# BMS_Cell.net
KiCad netlist of a schematic drawn in Altium Designer
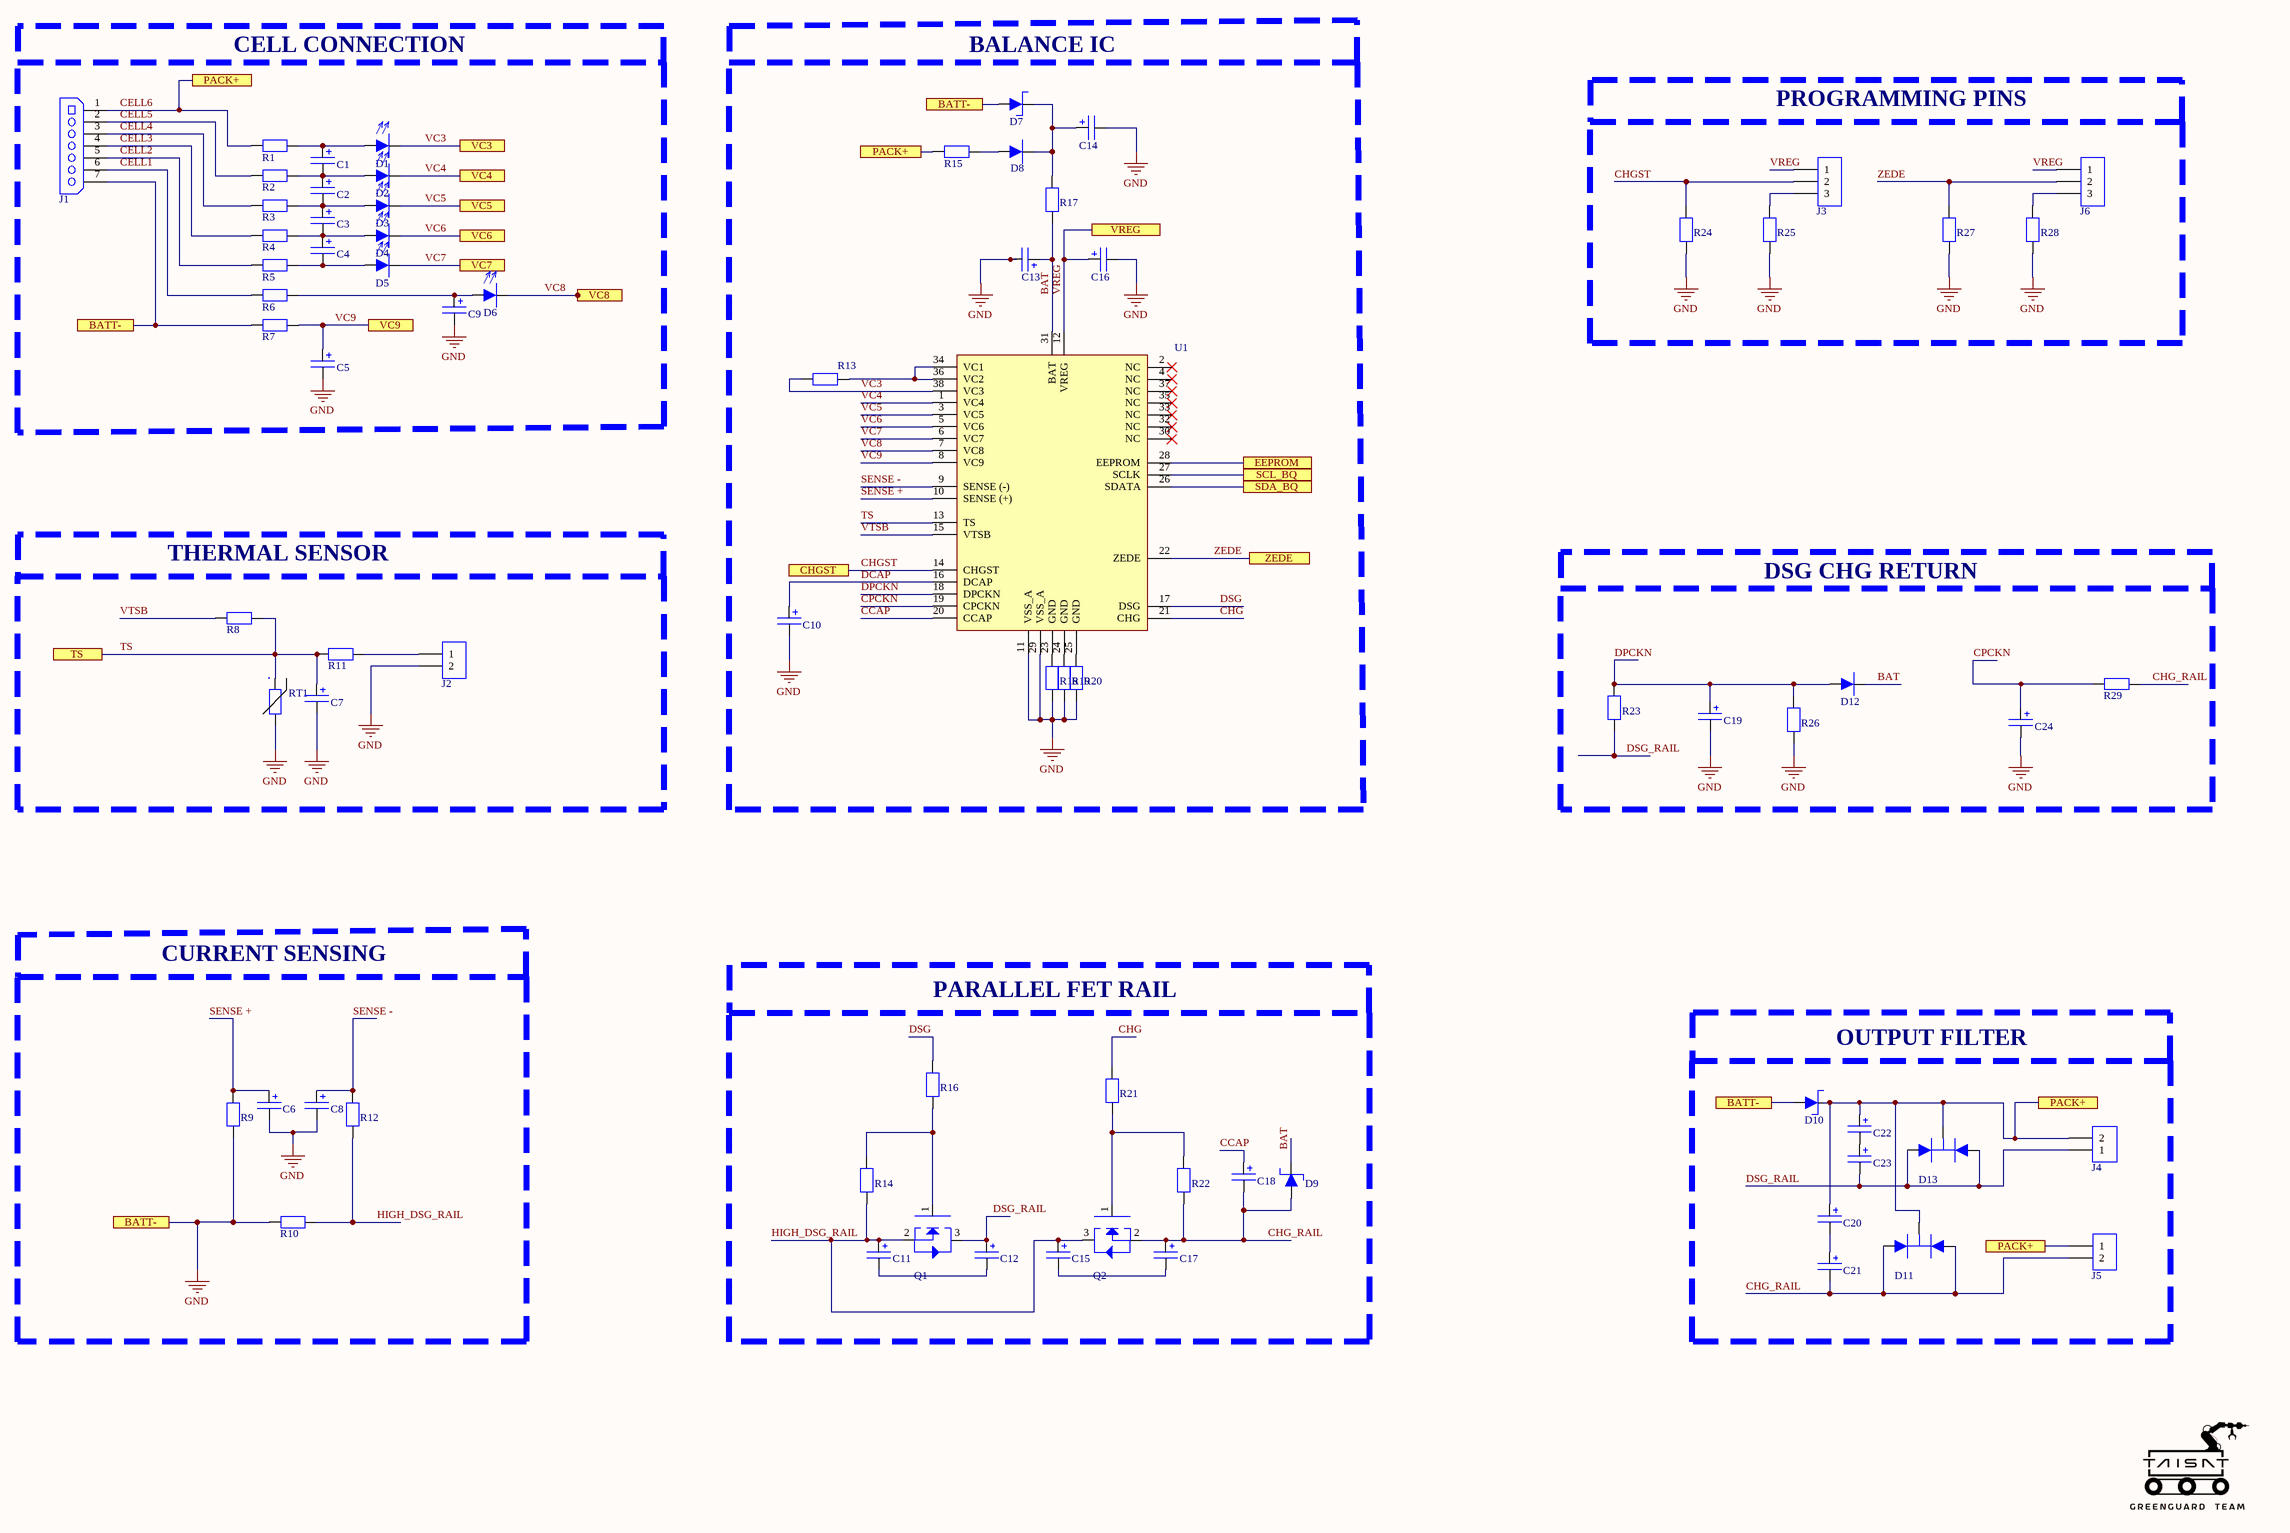
[diagram p0: BMS_Cell.SchDoc]

(export (version "E")
  (design (tool "Eeschema 10.0.6"))
  (components
    (comp (ref "C1")
      (value "1uF")
      (footprint "CAP 0805")
      (description "Multilayer Ceramic Capacitor")
      (fields
        (field (name "MANUFACTURER") "KEMET")
        (field (name "MANUFACTURER PART NUMBER") "C0805C224K5RACTU")
        (field (name "CREATED BY") "Kaptanyum")
      )
      (libsource (lib "Kaptanyums Lib") (part "CAP 0805"))
    )
    (comp (ref "C2")
      (value "1uF")
      (footprint "CAP 0805")
      (description "Multilayer Ceramic Capacitor")
      (fields
        (field (name "MANUFACTURER") "KEMET")
        (field (name "MANUFACTURER PART NUMBER") "C0805C224K5RACTU")
        (field (name "CREATED BY") "Kaptanyum")
      )
      (libsource (lib "Kaptanyums Lib") (part "CAP 0805"))
    )
    (comp (ref "C3")
      (value "1uF")
      (footprint "CAP 0805")
      (description "Multilayer Ceramic Capacitor")
      (fields
        (field (name "MANUFACTURER") "KEMET")
        (field (name "MANUFACTURER PART NUMBER") "C0805C224K5RACTU")
        (field (name "CREATED BY") "Kaptanyum")
      )
      (libsource (lib "Kaptanyums Lib") (part "CAP 0805"))
    )
    (comp (ref "C4")
      (value "1uF")
      (footprint "CAP 0805")
      (description "Multilayer Ceramic Capacitor")
      (fields
        (field (name "MANUFACTURER") "KEMET")
        (field (name "MANUFACTURER PART NUMBER") "C0805C224K5RACTU")
        (field (name "CREATED BY") "Kaptanyum")
      )
      (libsource (lib "Kaptanyums Lib") (part "CAP 0805"))
    )
    (comp (ref "C5")
      (value "1uF")
      (footprint "CAP 0805")
      (description "Multilayer Ceramic Capacitor")
      (fields
        (field (name "MANUFACTURER") "KEMET")
        (field (name "MANUFACTURER PART NUMBER") "C0805C224K5RACTU")
        (field (name "CREATED BY") "Kaptanyum")
      )
      (libsource (lib "Kaptanyums Lib") (part "CAP 0805"))
    )
    (comp (ref "C6")
      (value "0.1uF")
      (footprint "CAP 0603")
      (description "Multilayer Ceramic Capacitor")
      (fields
        (field (name "MANUFACTURER") "KEMET")
        (field (name "MANUFACTURER PART NUMBER") "C0603C103K5RACTU")
        (field (name "CREATED BY") "Kaptanyum")
      )
      (libsource (lib "Kaptanyums Lib") (part "CAP 0603"))
    )
    (comp (ref "C7")
      (value "10nF")
      (footprint "CAP 0603")
      (description "Multilayer Ceramic Capacitor")
      (fields
        (field (name "MANUFACTURER") "KEMET")
        (field (name "MANUFACTURER PART NUMBER") "C0603C103K5RACTU")
        (field (name "CREATED BY") "Kaptanyum")
      )
      (libsource (lib "Kaptanyums Lib") (part "CAP 0603"))
    )
    (comp (ref "C8")
      (value "0.1uF")
      (footprint "CAP 0603")
      (description "Multilayer Ceramic Capacitor")
      (fields
        (field (name "MANUFACTURER") "KEMET")
        (field (name "MANUFACTURER PART NUMBER") "C0603C103K5RACTU")
        (field (name "CREATED BY") "Kaptanyum")
      )
      (libsource (lib "Kaptanyums Lib") (part "CAP 0603"))
    )
    (comp (ref "C9")
      (value "1uF")
      (footprint "CAP 0805")
      (description "Multilayer Ceramic Capacitor")
      (fields
        (field (name "MANUFACTURER") "KEMET")
        (field (name "MANUFACTURER PART NUMBER") "C0805C224K5RACTU")
        (field (name "CREATED BY") "Kaptanyum")
      )
      (libsource (lib "Kaptanyums Lib") (part "CAP 0805"))
    )
    (comp (ref "C10")
      (value "1uF")
      (footprint "CAP 0603")
      (description "Multilayer Ceramic Capacitor")
      (fields
        (field (name "MANUFACTURER") "KEMET")
        (field (name "MANUFACTURER PART NUMBER") "C0603C103K5RACTU")
        (field (name "CREATED BY") "Kaptanyum")
      )
      (libsource (lib "Kaptanyums Lib") (part "CAP 0603"))
    )
    (comp (ref "C11")
      (value "0.1uF")
      (footprint "CAP 0603")
      (description "Multilayer Ceramic Capacitor")
      (fields
        (field (name "MANUFACTURER") "KEMET")
        (field (name "MANUFACTURER PART NUMBER") "C0603C103K5RACTU")
        (field (name "CREATED BY") "Kaptanyum")
      )
      (libsource (lib "Kaptanyums Lib") (part "CAP 0603"))
    )
    (comp (ref "C12")
      (value "0.1uF")
      (footprint "CAP 0603")
      (description "Multilayer Ceramic Capacitor")
      (fields
        (field (name "MANUFACTURER") "KEMET")
        (field (name "MANUFACTURER PART NUMBER") "C0603C103K5RACTU")
        (field (name "CREATED BY") "Kaptanyum")
      )
      (libsource (lib "Kaptanyums Lib") (part "CAP 0603"))
    )
    (comp (ref "C13")
      (value "0.1uF")
      (footprint "CAP 0603")
      (description "Multilayer Ceramic Capacitor")
      (fields
        (field (name "MANUFACTURER") "KEMET")
        (field (name "MANUFACTURER PART NUMBER") "C0603C103K5RACTU")
        (field (name "CREATED BY") "Kaptanyum")
      )
      (libsource (lib "Kaptanyums Lib") (part "CAP 0603"))
    )
    (comp (ref "C14")
      (value "10uF")
      (footprint "CAP 0603")
      (description "Multilayer Ceramic Capacitor")
      (fields
        (field (name "MANUFACTURER") "KEMET")
        (field (name "MANUFACTURER PART NUMBER") "C0603C103K5RACTU")
        (field (name "CREATED BY") "Kaptanyum")
      )
      (libsource (lib "Kaptanyums Lib") (part "CAP 0603"))
    )
    (comp (ref "C15")
      (value "0.1uF")
      (footprint "CAP 0603")
      (description "Multilayer Ceramic Capacitor")
      (fields
        (field (name "MANUFACTURER") "KEMET")
        (field (name "MANUFACTURER PART NUMBER") "C0603C103K5RACTU")
        (field (name "CREATED BY") "Kaptanyum")
      )
      (libsource (lib "Kaptanyums Lib") (part "CAP 0603"))
    )
    (comp (ref "C16")
      (value "4.7uF")
      (footprint "CAP 0603")
      (description "Multilayer Ceramic Capacitor")
      (fields
        (field (name "MANUFACTURER") "KEMET")
        (field (name "MANUFACTURER PART NUMBER") "C0603C103K5RACTU")
        (field (name "CREATED BY") "Kaptanyum")
      )
      (libsource (lib "Kaptanyums Lib") (part "CAP 0603"))
    )
    (comp (ref "C17")
      (value "0.1uF")
      (footprint "CAP 0603")
      (description "Multilayer Ceramic Capacitor")
      (fields
        (field (name "MANUFACTURER") "KEMET")
        (field (name "MANUFACTURER PART NUMBER") "C0603C103K5RACTU")
        (field (name "CREATED BY") "Kaptanyum")
      )
      (libsource (lib "Kaptanyums Lib") (part "CAP 0603"))
    )
    (comp (ref "C18")
      (value "1uF")
      (footprint "CAP 0603")
      (description "Multilayer Ceramic Capacitor")
      (fields
        (field (name "MANUFACTURER") "KEMET")
        (field (name "MANUFACTURER PART NUMBER") "C0603C103K5RACTU")
        (field (name "CREATED BY") "Kaptanyum")
      )
      (libsource (lib "Kaptanyums Lib") (part "CAP 0603"))
    )
    (comp (ref "C19")
      (value "0.1uF")
      (footprint "CAP 0603")
      (description "Multilayer Ceramic Capacitor")
      (fields
        (field (name "MANUFACTURER") "KEMET")
        (field (name "MANUFACTURER PART NUMBER") "C0603C103K5RACTU")
        (field (name "CREATED BY") "Kaptanyum")
      )
      (libsource (lib "Kaptanyums Lib") (part "CAP 0603"))
    )
    (comp (ref "C20")
      (value "0.1uF")
      (footprint "CAP 0603")
      (description "Multilayer Ceramic Capacitor")
      (fields
        (field (name "MANUFACTURER") "KEMET")
        (field (name "MANUFACTURER PART NUMBER") "C0603C103K5RACTU")
        (field (name "CREATED BY") "Kaptanyum")
      )
      (libsource (lib "Kaptanyums Lib") (part "CAP 0603"))
    )
    (comp (ref "C21")
      (value "0.1uF")
      (footprint "CAP 0603")
      (description "Multilayer Ceramic Capacitor")
      (fields
        (field (name "MANUFACTURER") "KEMET")
        (field (name "MANUFACTURER PART NUMBER") "C0603C103K5RACTU")
        (field (name "CREATED BY") "Kaptanyum")
      )
      (libsource (lib "Kaptanyums Lib") (part "CAP 0603"))
    )
    (comp (ref "C22")
      (value "0.1uF")
      (footprint "CAP 0603")
      (description "Multilayer Ceramic Capacitor")
      (fields
        (field (name "MANUFACTURER") "KEMET")
        (field (name "MANUFACTURER PART NUMBER") "C0603C103K5RACTU")
        (field (name "CREATED BY") "Kaptanyum")
      )
      (libsource (lib "Kaptanyums Lib") (part "CAP 0603"))
    )
    (comp (ref "C23")
      (value "0.1uF")
      (footprint "CAP 0603")
      (description "Multilayer Ceramic Capacitor")
      (fields
        (field (name "MANUFACTURER") "KEMET")
        (field (name "MANUFACTURER PART NUMBER") "C0603C103K5RACTU")
        (field (name "CREATED BY") "Kaptanyum")
      )
      (libsource (lib "Kaptanyums Lib") (part "CAP 0603"))
    )
    (comp (ref "C24")
      (value "0.1uF")
      (footprint "CAP 0603")
      (description "Multilayer Ceramic Capacitor")
      (fields
        (field (name "MANUFACTURER") "KEMET")
        (field (name "MANUFACTURER PART NUMBER") "C0603C103K5RACTU")
        (field (name "CREATED BY") "Kaptanyum")
      )
      (libsource (lib "Kaptanyums Lib") (part "CAP 0603"))
    )
    (comp (ref "D1")
      (value "LTW-C191TLA")
      (footprint "LED 0603")
      (description "Chip LED")
      (fields
        (field (name "MANUFACTURER") "Vishay Lite-On")
        (field (name "MANUFACTURER PART NUMBER") "LTST-C190GKT")
        (field (name "CREATED BY") "Kaptanyum")
      )
      (libsource (lib "Schlib") (part "LED 0603"))
    )
    (comp (ref "D2")
      (value "LTW-C191TLA")
      (footprint "LED 0603")
      (description "Chip LED")
      (fields
        (field (name "MANUFACTURER") "Vishay Lite-On")
        (field (name "MANUFACTURER PART NUMBER") "LTST-C190GKT")
        (field (name "CREATED BY") "Kaptanyum")
      )
      (libsource (lib "Schlib") (part "LED 0603"))
    )
    (comp (ref "D3")
      (value "LTW-C191TLA")
      (footprint "LED 0603")
      (description "Chip LED")
      (fields
        (field (name "MANUFACTURER") "Vishay Lite-On")
        (field (name "MANUFACTURER PART NUMBER") "LTST-C190GKT")
        (field (name "CREATED BY") "Kaptanyum")
      )
      (libsource (lib "Schlib") (part "LED 0603"))
    )
    (comp (ref "D4")
      (value "LTW-C191TLA")
      (footprint "LED 0603")
      (description "Chip LED")
      (fields
        (field (name "MANUFACTURER") "Vishay Lite-On")
        (field (name "MANUFACTURER PART NUMBER") "LTST-C190GKT")
        (field (name "CREATED BY") "Kaptanyum")
      )
      (libsource (lib "Schlib") (part "LED 0603"))
    )
    (comp (ref "D5")
      (value "LTW-C191TLA")
      (footprint "LED 0603")
      (description "Chip LED")
      (fields
        (field (name "MANUFACTURER") "Vishay Lite-On")
        (field (name "MANUFACTURER PART NUMBER") "LTST-C190GKT")
        (field (name "CREATED BY") "Kaptanyum")
      )
      (libsource (lib "Schlib") (part "LED 0603"))
    )
    (comp (ref "D6")
      (value "LTW-C191TLA")
      (footprint "LED 0603")
      (description "Chip LED")
      (fields
        (field (name "MANUFACTURER") "Vishay Lite-On")
        (field (name "MANUFACTURER PART NUMBER") "LTST-C190GKT")
        (field (name "CREATED BY") "Kaptanyum")
      )
      (libsource (lib "Schlib") (part "LED 0603"))
    )
    (comp (ref "D7")
      (value "SMAJ36A-HT")
      (footprint "DO214AC")
      (description "Diode TVS 36V")
      (fields
        (field (name "MANUFACTURER") "Vishay Semiconductors")
        (field (name "MANUFACTURER PART NUMBER") "SMAJ36AHE3/61")
      )
      (libsource (lib "Schlib") (part "SMAJ36A-HT"))
    )
    (comp (ref "D8")
      (value "1N4148WS-HT")
      (footprint "SOD323")
      (description "Diode Switch 75V")
      (libsource (lib "Kaptanyums Lib") (part "1N4148WS-HT"))
    )
    (comp (ref "D9")
      (value "SMAJ36A-HT")
      (footprint "DO214AC")
      (description "Diode TVS 36V")
      (fields
        (field (name "MANUFACTURER") "Vishay Semiconductors")
        (field (name "MANUFACTURER PART NUMBER") "SMAJ36AHE3/61")
      )
      (libsource (lib "Schlib") (part "SMAJ36A-HT"))
    )
    (comp (ref "D10")
      (value "SMAJ36A-HT")
      (footprint "DO214AC")
      (description "Diode TVS 36V")
      (fields
        (field (name "MANUFACTURER") "Vishay Semiconductors")
        (field (name "MANUFACTURER PART NUMBER") "SMAJ36AHE3/61")
      )
      (libsource (lib "Schlib") (part "SMAJ36A-HT"))
    )
    (comp (ref "D11")
      (value "BYQ28ED")
      (footprint "DPAK")
      (description "Diode Array Rectifier")
      (fields
        (field (name "MANUFACTURER") "NXP Semiconductors")
        (field (name "MANUFACTURER PART NUMBER") "BYQ28ED-200/T3")
        (field (name "CREATED BY") "Kaptanyum")
      )
      (libsource (lib "Kaptanyums Lib") (part "BYQ28ED"))
    )
    (comp (ref "D12")
      (value "1N4148WS-HT")
      (footprint "SOD323")
      (description "Diode Switch 75V")
      (libsource (lib "Kaptanyums Lib") (part "1N4148WS-HT"))
    )
    (comp (ref "D13")
      (value "BYQ28ED")
      (footprint "DPAK")
      (description "Diode Array Rectifier")
      (fields
        (field (name "MANUFACTURER") "NXP Semiconductors")
        (field (name "MANUFACTURER PART NUMBER") "BYQ28ED-200/T3")
        (field (name "CREATED BY") "Kaptanyum")
      )
      (libsource (lib "Kaptanyums Lib") (part "BYQ28ED"))
    )
    (comp (ref "J1")
      (value "JST-XH-7")
      (footprint "JST-XH-7")
      (description "JST Socket for PCB")
      (fields
        (field (name "MANUFACTURER") "JST")
        (field (name "MANUFACTURER PART NUMBER") "B4B-XH-A(LF)(SN)")
        (field (name "CREATED BY") "Kaptanyum")
      )
      (libsource (lib "Kaptanyums Lib") (part "JST-XH-7"))
    )
    (comp (ref "J2")
      (value "146285-2")
      (footprint "HEADER 1x2")
      (description "Header for PCB")
      (fields
        (field (name "MANUFACTURER") "JST")
        (field (name "MANUFACTURER PART NUMBER") "B4B-XH-A(LF)(SN)")
        (field (name "CREATED BY") "Kaptanyum")
      )
      (libsource (lib "Kaptanyums Lib") (part "HEADER 1x2"))
    )
    (comp (ref "J3")
      (value "146285-3")
      (footprint "HEADER 1x3")
      (description "Header for PCB")
      (fields
        (field (name "MANUFACTURER") "JST")
        (field (name "MANUFACTURER PART NUMBER") "B4B-XH-A(LF)(SN)")
        (field (name "CREATED BY") "Kaptanyum")
      )
      (libsource (lib "Kaptanyums Lib") (part "HEADER 1x3"))
    )
    (comp (ref "J4")
      (value "282845-2")
      (footprint "Terminal 1x2")
      (description "7.62mm 2 POS")
      (fields (field (name "CREATED BY") "Kaptanyum"))
      (libsource (lib "Kaptanyums Lib") (part "SCREW TERMINAL"))
    )
    (comp (ref "J5")
      (value "282845-2")
      (footprint "Terminal 1x2")
      (description "7.62mm 2 POS")
      (fields (field (name "CREATED BY") "Kaptanyum"))
      (libsource (lib "Kaptanyums Lib") (part "SCREW TERMINAL"))
    )
    (comp (ref "J6")
      (value "146285-3")
      (footprint "HEADER 1x3")
      (description "Header for PCB")
      (fields
        (field (name "MANUFACTURER") "JST")
        (field (name "MANUFACTURER PART NUMBER") "B4B-XH-A(LF)(SN)")
        (field (name "CREATED BY") "Kaptanyum")
      )
      (libsource (lib "Kaptanyums Lib") (part "HEADER 1x3"))
    )
    (comp (ref "Q1")
      (value "IRF540SPBF")
      (footprint "D2PAK-3")
      (description "MOSFET N-ch, 100V 28A")
      (libsource (lib "Kaptanyums Lib") (part "IRF540SPBF"))
    )
    (comp (ref "Q2")
      (value "IRF540SPBF")
      (footprint "D2PAK-3")
      (description "MOSFET N-ch, 100V 28A")
      (libsource (lib "Kaptanyums Lib") (part "IRF540SPBF"))
    )
    (comp (ref "R1")
      (value "500R")
      (footprint "RESISTOR 1206")
      (description "SMD Chip Resistor")
      (fields
        (field (name "MANUFACTURER") "Yageo")
        (field (name "MANUFACTURER PART NUMBER") "RC1206FR-074K7L")
        (field (name "CREATED BY") "Kaptanyum")
      )
      (libsource (lib "Kaptanyums Lib") (part "RES 1206"))
    )
    (comp (ref "R2")
      (value "500R")
      (footprint "RESISTOR 1206")
      (description "SMD Chip Resistor")
      (fields
        (field (name "MANUFACTURER") "Yageo")
        (field (name "MANUFACTURER PART NUMBER") "RC1206FR-074K7L")
        (field (name "CREATED BY") "Kaptanyum")
      )
      (libsource (lib "Kaptanyums Lib") (part "RES 1206"))
    )
    (comp (ref "R3")
      (value "500R")
      (footprint "RESISTOR 1206")
      (description "SMD Chip Resistor")
      (fields
        (field (name "MANUFACTURER") "Yageo")
        (field (name "MANUFACTURER PART NUMBER") "RC1206FR-074K7L")
        (field (name "CREATED BY") "Kaptanyum")
      )
      (libsource (lib "Kaptanyums Lib") (part "RES 1206"))
    )
    (comp (ref "R4")
      (value "500R")
      (footprint "RESISTOR 1206")
      (description "SMD Chip Resistor")
      (fields
        (field (name "MANUFACTURER") "Yageo")
        (field (name "MANUFACTURER PART NUMBER") "RC1206FR-074K7L")
        (field (name "CREATED BY") "Kaptanyum")
      )
      (libsource (lib "Kaptanyums Lib") (part "RES 1206"))
    )
    (comp (ref "R5")
      (value "500R")
      (footprint "RESISTOR 1206")
      (description "SMD Chip Resistor")
      (fields
        (field (name "MANUFACTURER") "Yageo")
        (field (name "MANUFACTURER PART NUMBER") "RC1206FR-074K7L")
        (field (name "CREATED BY") "Kaptanyum")
      )
      (libsource (lib "Kaptanyums Lib") (part "RES 1206"))
    )
    (comp (ref "R6")
      (value "500R")
      (footprint "RESISTOR 1206")
      (description "SMD Chip Resistor")
      (fields
        (field (name "MANUFACTURER") "Yageo")
        (field (name "MANUFACTURER PART NUMBER") "RC1206FR-074K7L")
        (field (name "CREATED BY") "Kaptanyum")
      )
      (libsource (lib "Kaptanyums Lib") (part "RES 1206"))
    )
    (comp (ref "R7")
      (value "500R")
      (footprint "RESISTOR 1206")
      (description "SMD Chip Resistor")
      (fields
        (field (name "MANUFACTURER") "Yageo")
        (field (name "MANUFACTURER PART NUMBER") "RC1206FR-074K7L")
        (field (name "CREATED BY") "Kaptanyum")
      )
      (libsource (lib "Kaptanyums Lib") (part "RES 1206"))
    )
    (comp (ref "R8")
      (value "10K")
      (footprint "RESISTOR 0603")
      (description "SMD Chip Resistor")
      (fields
        (field (name "MANUFACTURER") "Yageo")
        (field (name "MANUFACTURER PART NUMBER") "AC0603FR-071KL")
        (field (name "CREATED BY") "Kaptanyum")
      )
      (libsource (lib "Kaptanyums Lib") (part "RES 0603"))
    )
    (comp (ref "R9")
      (value "1K")
      (footprint "RESISTOR 0603")
      (description "SMD Chip Resistor")
      (fields
        (field (name "MANUFACTURER") "Yageo")
        (field (name "MANUFACTURER PART NUMBER") "AC0603FR-071KL")
        (field (name "CREATED BY") "Kaptanyum")
      )
      (libsource (lib "Kaptanyums Lib") (part "RES 0603"))
    )
    (comp (ref "R10")
      (value "0.002R Shunt")
      (footprint "RESISTOR 2512")
      (description "SMD Chip Resistor")
      (fields
        (field (name "MANUFACTURER") "Yageo")
        (field (name "MANUFACTURER PART NUMBER") "RC1206FR-074K7L")
        (field (name "CREATED BY") "Kaptanyum")
      )
      (libsource (lib "Kaptanyums Lib") (part "RES 2512"))
    )
    (comp (ref "R11")
      (value "50R")
      (footprint "RESISTOR 0603")
      (description "SMD Chip Resistor")
      (fields
        (field (name "MANUFACTURER") "Yageo")
        (field (name "MANUFACTURER PART NUMBER") "AC0603FR-071KL")
        (field (name "CREATED BY") "Kaptanyum")
      )
      (libsource (lib "Kaptanyums Lib") (part "RES 0603"))
    )
    (comp (ref "R12")
      (value "1K")
      (footprint "RESISTOR 0603")
      (description "SMD Chip Resistor")
      (fields
        (field (name "MANUFACTURER") "Yageo")
        (field (name "MANUFACTURER PART NUMBER") "AC0603FR-071KL")
        (field (name "CREATED BY") "Kaptanyum")
      )
      (libsource (lib "Kaptanyums Lib") (part "RES 0603"))
    )
    (comp (ref "R13")
      (value "100R")
      (footprint "RESISTOR 0603")
      (description "SMD Chip Resistor")
      (fields
        (field (name "MANUFACTURER") "Yageo")
        (field (name "MANUFACTURER PART NUMBER") "AC0603FR-071KL")
        (field (name "CREATED BY") "Kaptanyum")
      )
      (libsource (lib "Kaptanyums Lib") (part "RES 0603"))
    )
    (comp (ref "R14")
      (value "5.1M")
      (footprint "RESISTOR 0603")
      (description "SMD Chip Resistor")
      (fields
        (field (name "MANUFACTURER") "Yageo")
        (field (name "MANUFACTURER PART NUMBER") "AC0603FR-071KL")
        (field (name "CREATED BY") "Kaptanyum")
      )
      (libsource (lib "Kaptanyums Lib") (part "RES 0603"))
    )
    (comp (ref "R15")
      (value "200R")
      (footprint "RESISTOR 0603")
      (description "SMD Chip Resistor")
      (fields
        (field (name "MANUFACTURER") "Yageo")
        (field (name "MANUFACTURER PART NUMBER") "AC0603FR-071KL")
        (field (name "CREATED BY") "Kaptanyum")
      )
      (libsource (lib "Kaptanyums Lib") (part "RES 0603"))
    )
    (comp (ref "R16")
      (value "1K")
      (footprint "RESISTOR 0603")
      (description "SMD Chip Resistor")
      (fields
        (field (name "MANUFACTURER") "Yageo")
        (field (name "MANUFACTURER PART NUMBER") "AC0603FR-071KL")
        (field (name "CREATED BY") "Kaptanyum")
      )
      (libsource (lib "Kaptanyums Lib") (part "RES 0603"))
    )
    (comp (ref "R17")
      (value "100R")
      (footprint "RESISTOR 0603")
      (description "SMD Chip Resistor")
      (fields
        (field (name "MANUFACTURER") "Yageo")
        (field (name "MANUFACTURER PART NUMBER") "AC0603FR-071KL")
        (field (name "CREATED BY") "Kaptanyum")
      )
      (libsource (lib "Kaptanyums Lib") (part "RES 0603"))
    )
    (comp (ref "R18")
      (value "1K")
      (footprint "RESISTOR 0603")
      (description "SMD Chip Resistor")
      (fields
        (field (name "MANUFACTURER") "Yageo")
        (field (name "MANUFACTURER PART NUMBER") "AC0603FR-071KL")
        (field (name "CREATED BY") "Kaptanyum")
      )
      (libsource (lib "Kaptanyums Lib") (part "RES 0603"))
    )
    (comp (ref "R19")
      (value "1K")
      (footprint "RESISTOR 0603")
      (description "SMD Chip Resistor")
      (fields
        (field (name "MANUFACTURER") "Yageo")
        (field (name "MANUFACTURER PART NUMBER") "AC0603FR-071KL")
        (field (name "CREATED BY") "Kaptanyum")
      )
      (libsource (lib "Kaptanyums Lib") (part "RES 0603"))
    )
    (comp (ref "R20")
      (value "1K")
      (footprint "RESISTOR 0603")
      (description "SMD Chip Resistor")
      (fields
        (field (name "MANUFACTURER") "Yageo")
        (field (name "MANUFACTURER PART NUMBER") "AC0603FR-071KL")
        (field (name "CREATED BY") "Kaptanyum")
      )
      (libsource (lib "Kaptanyums Lib") (part "RES 0603"))
    )
    (comp (ref "R21")
      (value "1K")
      (footprint "RESISTOR 0603")
      (description "SMD Chip Resistor")
      (fields
        (field (name "MANUFACTURER") "Yageo")
        (field (name "MANUFACTURER PART NUMBER") "AC0603FR-071KL")
        (field (name "CREATED BY") "Kaptanyum")
      )
      (libsource (lib "Kaptanyums Lib") (part "RES 0603"))
    )
    (comp (ref "R22")
      (value "5.1M")
      (footprint "RESISTOR 0603")
      (description "SMD Chip Resistor")
      (fields
        (field (name "MANUFACTURER") "Yageo")
        (field (name "MANUFACTURER PART NUMBER") "AC0603FR-071KL")
        (field (name "CREATED BY") "Kaptanyum")
      )
      (libsource (lib "Kaptanyums Lib") (part "RES 0603"))
    )
    (comp (ref "R23")
      (value "100R")
      (footprint "RESISTOR 0603")
      (description "SMD Chip Resistor")
      (fields
        (field (name "MANUFACTURER") "Yageo")
        (field (name "MANUFACTURER PART NUMBER") "AC0603FR-071KL")
        (field (name "CREATED BY") "Kaptanyum")
      )
      (libsource (lib "Kaptanyums Lib") (part "RES 0603"))
    )
    (comp (ref "R24")
      (value "1K")
      (footprint "RESISTOR 0603")
      (description "SMD Chip Resistor")
      (fields
        (field (name "MANUFACTURER") "Yageo")
        (field (name "MANUFACTURER PART NUMBER") "AC0603FR-071KL")
        (field (name "CREATED BY") "Kaptanyum")
      )
      (libsource (lib "Kaptanyums Lib") (part "RES 0603"))
    )
    (comp (ref "R25")
      (value "1K")
      (footprint "RESISTOR 0603")
      (description "SMD Chip Resistor")
      (fields
        (field (name "MANUFACTURER") "Yageo")
        (field (name "MANUFACTURER PART NUMBER") "AC0603FR-071KL")
        (field (name "CREATED BY") "Kaptanyum")
      )
      (libsource (lib "Kaptanyums Lib") (part "RES 0603"))
    )
    (comp (ref "R26")
      (value "47K")
      (footprint "RESISTOR 0603")
      (description "SMD Chip Resistor")
      (fields
        (field (name "MANUFACTURER") "Yageo")
        (field (name "MANUFACTURER PART NUMBER") "AC0603FR-071KL")
        (field (name "CREATED BY") "Kaptanyum")
      )
      (libsource (lib "Kaptanyums Lib") (part "RES 0603"))
    )
    (comp (ref "R27")
      (value "1K")
      (footprint "RESISTOR 0603")
      (description "SMD Chip Resistor")
      (fields
        (field (name "MANUFACTURER") "Yageo")
        (field (name "MANUFACTURER PART NUMBER") "AC0603FR-071KL")
        (field (name "CREATED BY") "Kaptanyum")
      )
      (libsource (lib "Kaptanyums Lib") (part "RES 0603"))
    )
    (comp (ref "R28")
      (value "1K")
      (footprint "RESISTOR 0603")
      (description "SMD Chip Resistor")
      (fields
        (field (name "MANUFACTURER") "Yageo")
        (field (name "MANUFACTURER PART NUMBER") "AC0603FR-071KL")
        (field (name "CREATED BY") "Kaptanyum")
      )
      (libsource (lib "Kaptanyums Lib") (part "RES 0603"))
    )
    (comp (ref "R29")
      (value "100R")
      (footprint "RESISTOR 0603")
      (description "SMD Chip Resistor")
      (fields
        (field (name "MANUFACTURER") "Yageo")
        (field (name "MANUFACTURER PART NUMBER") "AC0603FR-071KL")
        (field (name "CREATED BY") "Kaptanyum")
      )
      (libsource (lib "Kaptanyums Lib") (part "RES 0603"))
    )
    (comp (ref "RT1")
      (value "10K")
      (footprint "NTC 0603")
      (description "Thermistor NTC")
      (fields
        (field (name "MANUFACTURER") "Panasonic")
        (field (name "MANUFACTURER PART NUMBER") "ERT-J1VG103FA")
        (field (name "CREATED BY") "Kaptanyum")
      )
      (libsource (lib "Kaptanyums Lib") (part "NTC 0603"))
    )
    (comp (ref "U1")
      (value "BQ77908")
      (footprint "TSSOP-38")
      (description "Cell Balance, Cell Monitoring")
      (fields
        (field (name "MANUFACTURER") "Texas Instruments")
        (field (name "MANUFACTURER PART NUMBER") "BQ77908ADBTR")
        (field (name "CREATED BY") "Kaptanyum")
      )
      (libsource (lib "Kaptanyums Lib") (part "BQ77908"))
    )
  )
  (nets
    (net (code "1") (name "/BAT") (class "Default")
      (node (ref "C13") (pin "1") (pinfunction "1_1") (pintype "passive"))
      (node (ref "D12") (pin "1") (pinfunction "1_1") (pintype "passive"))
      (node (ref "D9") (pin "1") (pinfunction "1_1") (pintype "passive"))
      (node (ref "R17") (pin "1") (pinfunction "1_1") (pintype "passive"))
      (node (ref "U1") (pin "31") (pinfunction "BAT_31") (pintype "passive"))
    )
    (net (code "2") (name "/CCAP") (class "Default")
      (node (ref "C18") (pin "1") (pinfunction "1_1") (pintype "passive"))
      (node (ref "U1") (pin "20") (pinfunction "CCAP_20") (pintype "passive"))
    )
    (net (code "3") (name "/CELL1") (class "Default")
      (node (ref "J1") (pin "6") (pinfunction "6_6") (pintype "passive"))
      (node (ref "R6") (pin "1") (pinfunction "1_1") (pintype "passive"))
    )
    (net (code "4") (name "/CELL2") (class "Default")
      (node (ref "J1") (pin "5") (pinfunction "5_5") (pintype "passive"))
      (node (ref "R5") (pin "1") (pinfunction "1_1") (pintype "passive"))
    )
    (net (code "5") (name "/CELL3") (class "Default")
      (node (ref "J1") (pin "4") (pinfunction "4_4") (pintype "passive"))
      (node (ref "R4") (pin "1") (pinfunction "1_1") (pintype "passive"))
    )
    (net (code "6") (name "/CELL4") (class "Default")
      (node (ref "J1") (pin "3") (pinfunction "3_3") (pintype "passive"))
      (node (ref "R3") (pin "1") (pinfunction "1_1") (pintype "passive"))
    )
    (net (code "7") (name "/CELL5") (class "Default")
      (node (ref "J1") (pin "2") (pinfunction "2_2") (pintype "passive"))
      (node (ref "R2") (pin "1") (pinfunction "1_1") (pintype "passive"))
    )
    (net (code "8") (name "/CELL6") (class "Default")
      (node (ref "C20") (pin "1") (pinfunction "1_1") (pintype "passive"))
      (node (ref "C22") (pin "1") (pinfunction "1_1") (pintype "passive"))
      (node (ref "D10") (pin "1") (pinfunction "1_1") (pintype "passive"))
      (node (ref "D11") (pin "2") (pinfunction "K_2") (pintype "passive"))
      (node (ref "D13") (pin "2") (pinfunction "K_2") (pintype "passive"))
      (node (ref "J1") (pin "1") (pinfunction "1_1") (pintype "passive"))
      (node (ref "J4") (pin "2") (pinfunction "2_2") (pintype "passive"))
      (node (ref "J5") (pin "1") (pinfunction "1_1") (pintype "passive"))
      (node (ref "R1") (pin "1") (pinfunction "1_1") (pintype "passive"))
      (node (ref "R15") (pin "2") (pinfunction "2_2") (pintype "passive"))
    )
    (net (code "9") (name "/CHG") (class "Default")
      (node (ref "R21") (pin "2") (pinfunction "2_2") (pintype "passive"))
      (node (ref "U1") (pin "21") (pinfunction "CHG_21") (pintype "passive"))
    )
    (net (code "10") (name "/CHGST") (class "Default")
      (node (ref "J3") (pin "2") (pinfunction "2_2") (pintype "passive"))
      (node (ref "R24") (pin "2") (pinfunction "2_2") (pintype "passive"))
      (node (ref "U1") (pin "14") (pinfunction "CHGST_14") (pintype "passive"))
    )
    (net (code "11") (name "/CHG_RAIL") (class "Default")
      (node (ref "C17") (pin "1") (pinfunction "1_1") (pintype "passive"))
      (node (ref "C18") (pin "2") (pinfunction "2_2") (pintype "passive"))
      (node (ref "C21") (pin "2") (pinfunction "2_2") (pintype "passive"))
      (node (ref "D11") (pin "1") (pinfunction "A1_1") (pintype "passive"))
      (node (ref "D11") (pin "3") (pinfunction "A2_3") (pintype "passive"))
      (node (ref "D9") (pin "2") (pinfunction "2_2") (pintype "passive"))
      (node (ref "J5") (pin "2") (pinfunction "2_2") (pintype "passive"))
      (node (ref "Q2") (pin "2") (pinfunction "S_2") (pintype "passive"))
      (node (ref "R22") (pin "1") (pinfunction "1_1") (pintype "passive"))
      (node (ref "R29") (pin "1") (pinfunction "1_1") (pintype "passive"))
    )
    (net (code "12") (name "/CPCKN") (class "Default")
      (node (ref "C24") (pin "1") (pinfunction "1_1") (pintype "passive"))
      (node (ref "R29") (pin "2") (pinfunction "2_2") (pintype "passive"))
      (node (ref "U1") (pin "19") (pinfunction "CPCKN_19") (pintype "passive"))
    )
    (net (code "13") (name "/DCAP") (class "Default")
      (node (ref "C10") (pin "1") (pinfunction "1_1") (pintype "passive"))
      (node (ref "U1") (pin "16") (pinfunction "DCAP_16") (pintype "passive"))
    )
    (net (code "14") (name "/DPCKN") (class "Default")
      (node (ref "C19") (pin "1") (pinfunction "1_1") (pintype "passive"))
      (node (ref "D12") (pin "2") (pinfunction "2_2") (pintype "passive"))
      (node (ref "R23") (pin "2") (pinfunction "2_2") (pintype "passive"))
      (node (ref "R26") (pin "2") (pinfunction "2_2") (pintype "passive"))
      (node (ref "U1") (pin "18") (pinfunction "DPCKN_18") (pintype "passive"))
    )
    (net (code "15") (name "/DSG") (class "Default")
      (node (ref "R16") (pin "2") (pinfunction "2_2") (pintype "passive"))
      (node (ref "U1") (pin "17") (pinfunction "DSG_17") (pintype "passive"))
    )
    (net (code "16") (name "/DSG_RAIL") (class "Default")
      (node (ref "C12") (pin "1") (pinfunction "1_1") (pintype "passive"))
      (node (ref "C23") (pin "2") (pinfunction "2_2") (pintype "passive"))
      (node (ref "D13") (pin "1") (pinfunction "A1_1") (pintype "passive"))
      (node (ref "D13") (pin "3") (pinfunction "A2_3") (pintype "passive"))
      (node (ref "J4") (pin "1") (pinfunction "1_1") (pintype "passive"))
      (node (ref "Q1") (pin "3") (pinfunction "D_3") (pintype "passive"))
      (node (ref "R23") (pin "1") (pinfunction "1_1") (pintype "passive"))
    )
    (net (code "17") (name "/EEPROM") (class "Default")
      (node (ref "U1") (pin "28") (pinfunction "EEPROM_28") (pintype "passive"))
    )
    (net (code "18") (name "/HIGH_DSG_RAIL") (class "Default")
      (node (ref "C11") (pin "1") (pinfunction "1_1") (pintype "passive"))
      (node (ref "C15") (pin "1") (pinfunction "1_1") (pintype "passive"))
      (node (ref "Q1") (pin "2") (pinfunction "S_2") (pintype "passive"))
      (node (ref "Q2") (pin "3") (pinfunction "D_3") (pintype "passive"))
      (node (ref "R10") (pin "2") (pinfunction "2_2") (pintype "passive"))
      (node (ref "R12") (pin "1") (pinfunction "1_1") (pintype "passive"))
      (node (ref "R14") (pin "1") (pinfunction "1_1") (pintype "passive"))
    )
    (net (code "19") (name "/SCL_BQ") (class "Default")
      (node (ref "U1") (pin "27") (pinfunction "SCLK_27") (pintype "passive"))
    )
    (net (code "20") (name "/SDA_BQ") (class "Default")
      (node (ref "U1") (pin "26") (pinfunction "SDATA_26") (pintype "passive"))
    )
    (net (code "21") (name "/SENSE +") (class "Default")
      (node (ref "C6") (pin "1") (pinfunction "1_1") (pintype "passive"))
      (node (ref "R9") (pin "2") (pinfunction "2_2") (pintype "passive"))
      (node (ref "U1") (pin "10") (pinfunction "SENSE_(+)_10") (pintype "passive"))
    )
    (net (code "22") (name "/SENSE -") (class "Default")
      (node (ref "C8") (pin "1") (pinfunction "1_1") (pintype "passive"))
      (node (ref "R12") (pin "2") (pinfunction "2_2") (pintype "passive"))
      (node (ref "U1") (pin "9") (pinfunction "SENSE_(-)_9") (pintype "passive"))
    )
    (net (code "23") (name "/TS") (class "Default")
      (node (ref "C7") (pin "1") (pinfunction "1_1") (pintype "passive"))
      (node (ref "R11") (pin "1") (pinfunction "1_1") (pintype "passive"))
      (node (ref "R8") (pin "2") (pinfunction "2_2") (pintype "passive"))
      (node (ref "RT1") (pin "1") (pinfunction "1_1") (pintype "passive"))
      (node (ref "U1") (pin "13") (pinfunction "TS_13") (pintype "passive"))
    )
    (net (code "24") (name "/VC3") (class "Default")
      (node (ref "D1") (pin "1") (pinfunction "1_1") (pintype "passive"))
      (node (ref "R13") (pin "1") (pinfunction "1_1") (pintype "passive"))
      (node (ref "U1") (pin "38") (pinfunction "VC3_38") (pintype "passive"))
    )
    (net (code "25") (name "/VC4") (class "Default")
      (node (ref "D2") (pin "1") (pinfunction "1_1") (pintype "passive"))
      (node (ref "U1") (pin "1") (pinfunction "VC4_1") (pintype "passive"))
    )
    (net (code "26") (name "/VC5") (class "Default")
      (node (ref "D3") (pin "1") (pinfunction "1_1") (pintype "passive"))
      (node (ref "U1") (pin "3") (pinfunction "VC5_3") (pintype "passive"))
    )
    (net (code "27") (name "/VC6") (class "Default")
      (node (ref "D4") (pin "1") (pinfunction "1_1") (pintype "passive"))
      (node (ref "U1") (pin "5") (pinfunction "VC6_5") (pintype "passive"))
    )
    (net (code "28") (name "/VC7") (class "Default")
      (node (ref "D5") (pin "1") (pinfunction "1_1") (pintype "passive"))
      (node (ref "U1") (pin "6") (pinfunction "VC7_6") (pintype "passive"))
    )
    (net (code "29") (name "/VC8") (class "Default")
      (node (ref "D6") (pin "1") (pinfunction "1_1") (pintype "passive"))
      (node (ref "U1") (pin "7") (pinfunction "VC8_7") (pintype "passive"))
    )
    (net (code "30") (name "/VC9") (class "Default")
      (node (ref "C5") (pin "1") (pinfunction "1_1") (pintype "passive"))
      (node (ref "R7") (pin "2") (pinfunction "2_2") (pintype "passive"))
      (node (ref "U1") (pin "8") (pinfunction "VC9_8") (pintype "passive"))
    )
    (net (code "31") (name "/VREG") (class "Default")
      (node (ref "C16") (pin "1") (pinfunction "1_1") (pintype "passive"))
      (node (ref "J3") (pin "1") (pinfunction "1_1") (pintype "passive"))
      (node (ref "J6") (pin "1") (pinfunction "1_1") (pintype "passive"))
      (node (ref "U1") (pin "12") (pinfunction "VREG_12") (pintype "passive"))
    )
    (net (code "32") (name "/VTSB") (class "Default")
      (node (ref "R8") (pin "1") (pinfunction "1_1") (pintype "passive"))
      (node (ref "U1") (pin "15") (pinfunction "VTSB_15") (pintype "passive"))
    )
    (net (code "33") (name "/ZEDE") (class "Default")
      (node (ref "J6") (pin "2") (pinfunction "2_2") (pintype "passive"))
      (node (ref "R27") (pin "2") (pinfunction "2_2") (pintype "passive"))
      (node (ref "U1") (pin "22") (pinfunction "ZEDE_22") (pintype "passive"))
    )
    (net (code "34") (name "GND") (class "Default")
      (node (ref "C10") (pin "2") (pinfunction "2_2") (pintype "passive"))
      (node (ref "C13") (pin "2") (pinfunction "2_2") (pintype "passive"))
      (node (ref "C14") (pin "2") (pinfunction "2_2") (pintype "passive"))
      (node (ref "C16") (pin "2") (pinfunction "2_2") (pintype "passive"))
      (node (ref "C19") (pin "2") (pinfunction "2_2") (pintype "passive"))
      (node (ref "C24") (pin "2") (pinfunction "2_2") (pintype "passive"))
      (node (ref "C5") (pin "2") (pinfunction "2_2") (pintype "passive"))
      (node (ref "C6") (pin "2") (pinfunction "2_2") (pintype "passive"))
      (node (ref "C7") (pin "2") (pinfunction "2_2") (pintype "passive"))
      (node (ref "C8") (pin "2") (pinfunction "2_2") (pintype "passive"))
      (node (ref "C9") (pin "2") (pinfunction "2_2") (pintype "passive"))
      (node (ref "D10") (pin "2") (pinfunction "2_2") (pintype "passive"))
      (node (ref "D7") (pin "2") (pinfunction "2_2") (pintype "passive"))
      (node (ref "J1") (pin "7") (pinfunction "7_7") (pintype "passive"))
      (node (ref "J2") (pin "2") (pinfunction "2_2") (pintype "passive"))
      (node (ref "R10") (pin "1") (pinfunction "1_1") (pintype "passive"))
      (node (ref "R18") (pin "1") (pinfunction "1_1") (pintype "passive"))
      (node (ref "R19") (pin "1") (pinfunction "1_1") (pintype "passive"))
      (node (ref "R20") (pin "1") (pinfunction "1_1") (pintype "passive"))
      (node (ref "R24") (pin "1") (pinfunction "1_1") (pintype "passive"))
      (node (ref "R25") (pin "1") (pinfunction "1_1") (pintype "passive"))
      (node (ref "R26") (pin "1") (pinfunction "1_1") (pintype "passive"))
      (node (ref "R27") (pin "1") (pinfunction "1_1") (pintype "passive"))
      (node (ref "R28") (pin "1") (pinfunction "1_1") (pintype "passive"))
      (node (ref "R7") (pin "1") (pinfunction "1_1") (pintype "passive"))
      (node (ref "R9") (pin "1") (pinfunction "1_1") (pintype "passive"))
      (node (ref "RT1") (pin "2") (pinfunction "2_2") (pintype "passive"))
      (node (ref "U1") (pin "11") (pinfunction "VSS_A_11") (pintype "passive"))
      (node (ref "U1") (pin "29") (pinfunction "VSS_A_29") (pintype "passive"))
    )
    (net (code "35") (name "Net-(C1-Pad1)") (class "Default")
      (node (ref "C1") (pin "1") (pinfunction "1_1") (pintype "passive"))
      (node (ref "D1") (pin "2") (pinfunction "2_2") (pintype "passive"))
      (node (ref "R1") (pin "2") (pinfunction "2_2") (pintype "passive"))
    )
    (net (code "36") (name "Net-(C1-Pad2)") (class "Default")
      (node (ref "C1") (pin "2") (pinfunction "2_2") (pintype "passive"))
      (node (ref "C2") (pin "1") (pinfunction "1_1") (pintype "passive"))
      (node (ref "D2") (pin "2") (pinfunction "2_2") (pintype "passive"))
      (node (ref "R2") (pin "2") (pinfunction "2_2") (pintype "passive"))
    )
    (net (code "37") (name "Net-(C2-Pad2)") (class "Default")
      (node (ref "C2") (pin "2") (pinfunction "2_2") (pintype "passive"))
      (node (ref "C3") (pin "1") (pinfunction "1_1") (pintype "passive"))
      (node (ref "D3") (pin "2") (pinfunction "2_2") (pintype "passive"))
      (node (ref "R3") (pin "2") (pinfunction "2_2") (pintype "passive"))
    )
    (net (code "38") (name "Net-(C3-Pad2)") (class "Default")
      (node (ref "C3") (pin "2") (pinfunction "2_2") (pintype "passive"))
      (node (ref "C4") (pin "1") (pinfunction "1_1") (pintype "passive"))
      (node (ref "D4") (pin "2") (pinfunction "2_2") (pintype "passive"))
      (node (ref "R4") (pin "2") (pinfunction "2_2") (pintype "passive"))
    )
    (net (code "39") (name "Net-(C4-Pad2)") (class "Default")
      (node (ref "C4") (pin "2") (pinfunction "2_2") (pintype "passive"))
      (node (ref "D5") (pin "2") (pinfunction "2_2") (pintype "passive"))
      (node (ref "R5") (pin "2") (pinfunction "2_2") (pintype "passive"))
    )
    (net (code "40") (name "Net-(C9-Pad1)") (class "Default")
      (node (ref "C9") (pin "1") (pinfunction "1_1") (pintype "passive"))
      (node (ref "D6") (pin "2") (pinfunction "2_2") (pintype "passive"))
      (node (ref "R6") (pin "2") (pinfunction "2_2") (pintype "passive"))
    )
    (net (code "41") (name "Net-(C11-Pad2)") (class "Default")
      (node (ref "C11") (pin "2") (pinfunction "2_2") (pintype "passive"))
      (node (ref "C12") (pin "2") (pinfunction "2_2") (pintype "passive"))
    )
    (net (code "42") (name "Net-(C14-Pad1)") (class "Default")
      (node (ref "C14") (pin "1") (pinfunction "1_1") (pintype "passive"))
      (node (ref "D7") (pin "1") (pinfunction "1_1") (pintype "passive"))
      (node (ref "D8") (pin "1") (pinfunction "1_1") (pintype "passive"))
      (node (ref "R17") (pin "2") (pinfunction "2_2") (pintype "passive"))
    )
    (net (code "43") (name "Net-(C15-Pad2)") (class "Default")
      (node (ref "C15") (pin "2") (pinfunction "2_2") (pintype "passive"))
      (node (ref "C17") (pin "2") (pinfunction "2_2") (pintype "passive"))
    )
    (net (code "44") (name "Net-(C20-Pad2)") (class "Default")
      (node (ref "C20") (pin "2") (pinfunction "2_2") (pintype "passive"))
      (node (ref "C21") (pin "1") (pinfunction "1_1") (pintype "passive"))
    )
    (net (code "45") (name "Net-(C22-Pad2)") (class "Default")
      (node (ref "C22") (pin "2") (pinfunction "2_2") (pintype "passive"))
      (node (ref "C23") (pin "1") (pinfunction "1_1") (pintype "passive"))
    )
    (net (code "46") (name "Net-(D8-Pad2)") (class "Default")
      (node (ref "D8") (pin "2") (pinfunction "2_2") (pintype "passive"))
      (node (ref "R15") (pin "1") (pinfunction "1_1") (pintype "passive"))
    )
    (net (code "47") (name "Net-(J2-Pad1)") (class "Default")
      (node (ref "J2") (pin "1") (pinfunction "1_1") (pintype "passive"))
      (node (ref "R11") (pin "2") (pinfunction "2_2") (pintype "passive"))
    )
    (net (code "48") (name "Net-(J3-Pad3)") (class "Default")
      (node (ref "J3") (pin "3") (pinfunction "3_3") (pintype "passive"))
      (node (ref "R25") (pin "2") (pinfunction "2_2") (pintype "passive"))
    )
    (net (code "49") (name "Net-(J6-Pad3)") (class "Default")
      (node (ref "J6") (pin "3") (pinfunction "3_3") (pintype "passive"))
      (node (ref "R28") (pin "2") (pinfunction "2_2") (pintype "passive"))
    )
    (net (code "50") (name "Net-(Q1-G)") (class "Default")
      (node (ref "Q1") (pin "1") (pinfunction "G_1") (pintype "passive"))
      (node (ref "R14") (pin "2") (pinfunction "2_2") (pintype "passive"))
      (node (ref "R16") (pin "1") (pinfunction "1_1") (pintype "passive"))
    )
    (net (code "51") (name "Net-(Q2-G)") (class "Default")
      (node (ref "Q2") (pin "1") (pinfunction "G_1") (pintype "passive"))
      (node (ref "R21") (pin "1") (pinfunction "1_1") (pintype "passive"))
      (node (ref "R22") (pin "2") (pinfunction "2_2") (pintype "passive"))
    )
    (net (code "52") (name "Net-(R18-Pad2)") (class "Default")
      (node (ref "R18") (pin "2") (pinfunction "2_2") (pintype "passive"))
      (node (ref "U1") (pin "23") (pinfunction "GND_23") (pintype "passive"))
    )
    (net (code "53") (name "Net-(R19-Pad2)") (class "Default")
      (node (ref "R19") (pin "2") (pinfunction "2_2") (pintype "passive"))
      (node (ref "U1") (pin "24") (pinfunction "GND_24") (pintype "passive"))
    )
    (net (code "54") (name "Net-(R20-Pad2)") (class "Default")
      (node (ref "R20") (pin "2") (pinfunction "2_2") (pintype "passive"))
      (node (ref "U1") (pin "25") (pinfunction "GND_25") (pintype "passive"))
    )
    (net (code "55") (name "Net-(U1-VC1)") (class "Default")
      (node (ref "R13") (pin "2") (pinfunction "2_2") (pintype "passive"))
      (node (ref "U1") (pin "34") (pinfunction "VC1_34") (pintype "passive"))
      (node (ref "U1") (pin "36") (pinfunction "VC2_36") (pintype "passive"))
    )
    (net (code "56") (name "unconnected-(U1-NC-Pad2)") (class "Default")
      (node (ref "U1") (pin "2") (pinfunction "NC_2") (pintype "passive+no_connect"))
    )
    (net (code "57") (name "unconnected-(U1-NC-Pad4)") (class "Default")
      (node (ref "U1") (pin "4") (pinfunction "NC_4") (pintype "passive+no_connect"))
    )
    (net (code "58") (name "unconnected-(U1-NC-Pad30)") (class "Default")
      (node (ref "U1") (pin "30") (pinfunction "NC_30") (pintype "passive+no_connect"))
    )
    (net (code "59") (name "unconnected-(U1-NC-Pad32)") (class "Default")
      (node (ref "U1") (pin "32") (pinfunction "NC_32") (pintype "passive+no_connect"))
    )
    (net (code "60") (name "unconnected-(U1-NC-Pad33)") (class "Default")
      (node (ref "U1") (pin "33") (pinfunction "NC_33") (pintype "passive+no_connect"))
    )
    (net (code "61") (name "unconnected-(U1-NC-Pad35)") (class "Default")
      (node (ref "U1") (pin "35") (pinfunction "NC_35") (pintype "passive+no_connect"))
    )
    (net (code "62") (name "unconnected-(U1-NC-Pad37)") (class "Default")
      (node (ref "U1") (pin "37") (pinfunction "NC_37") (pintype "passive+no_connect"))
    )
  )
)
